# WX0_007_102DL.net
KiCad netlist of a schematic drawn in Altium Designer
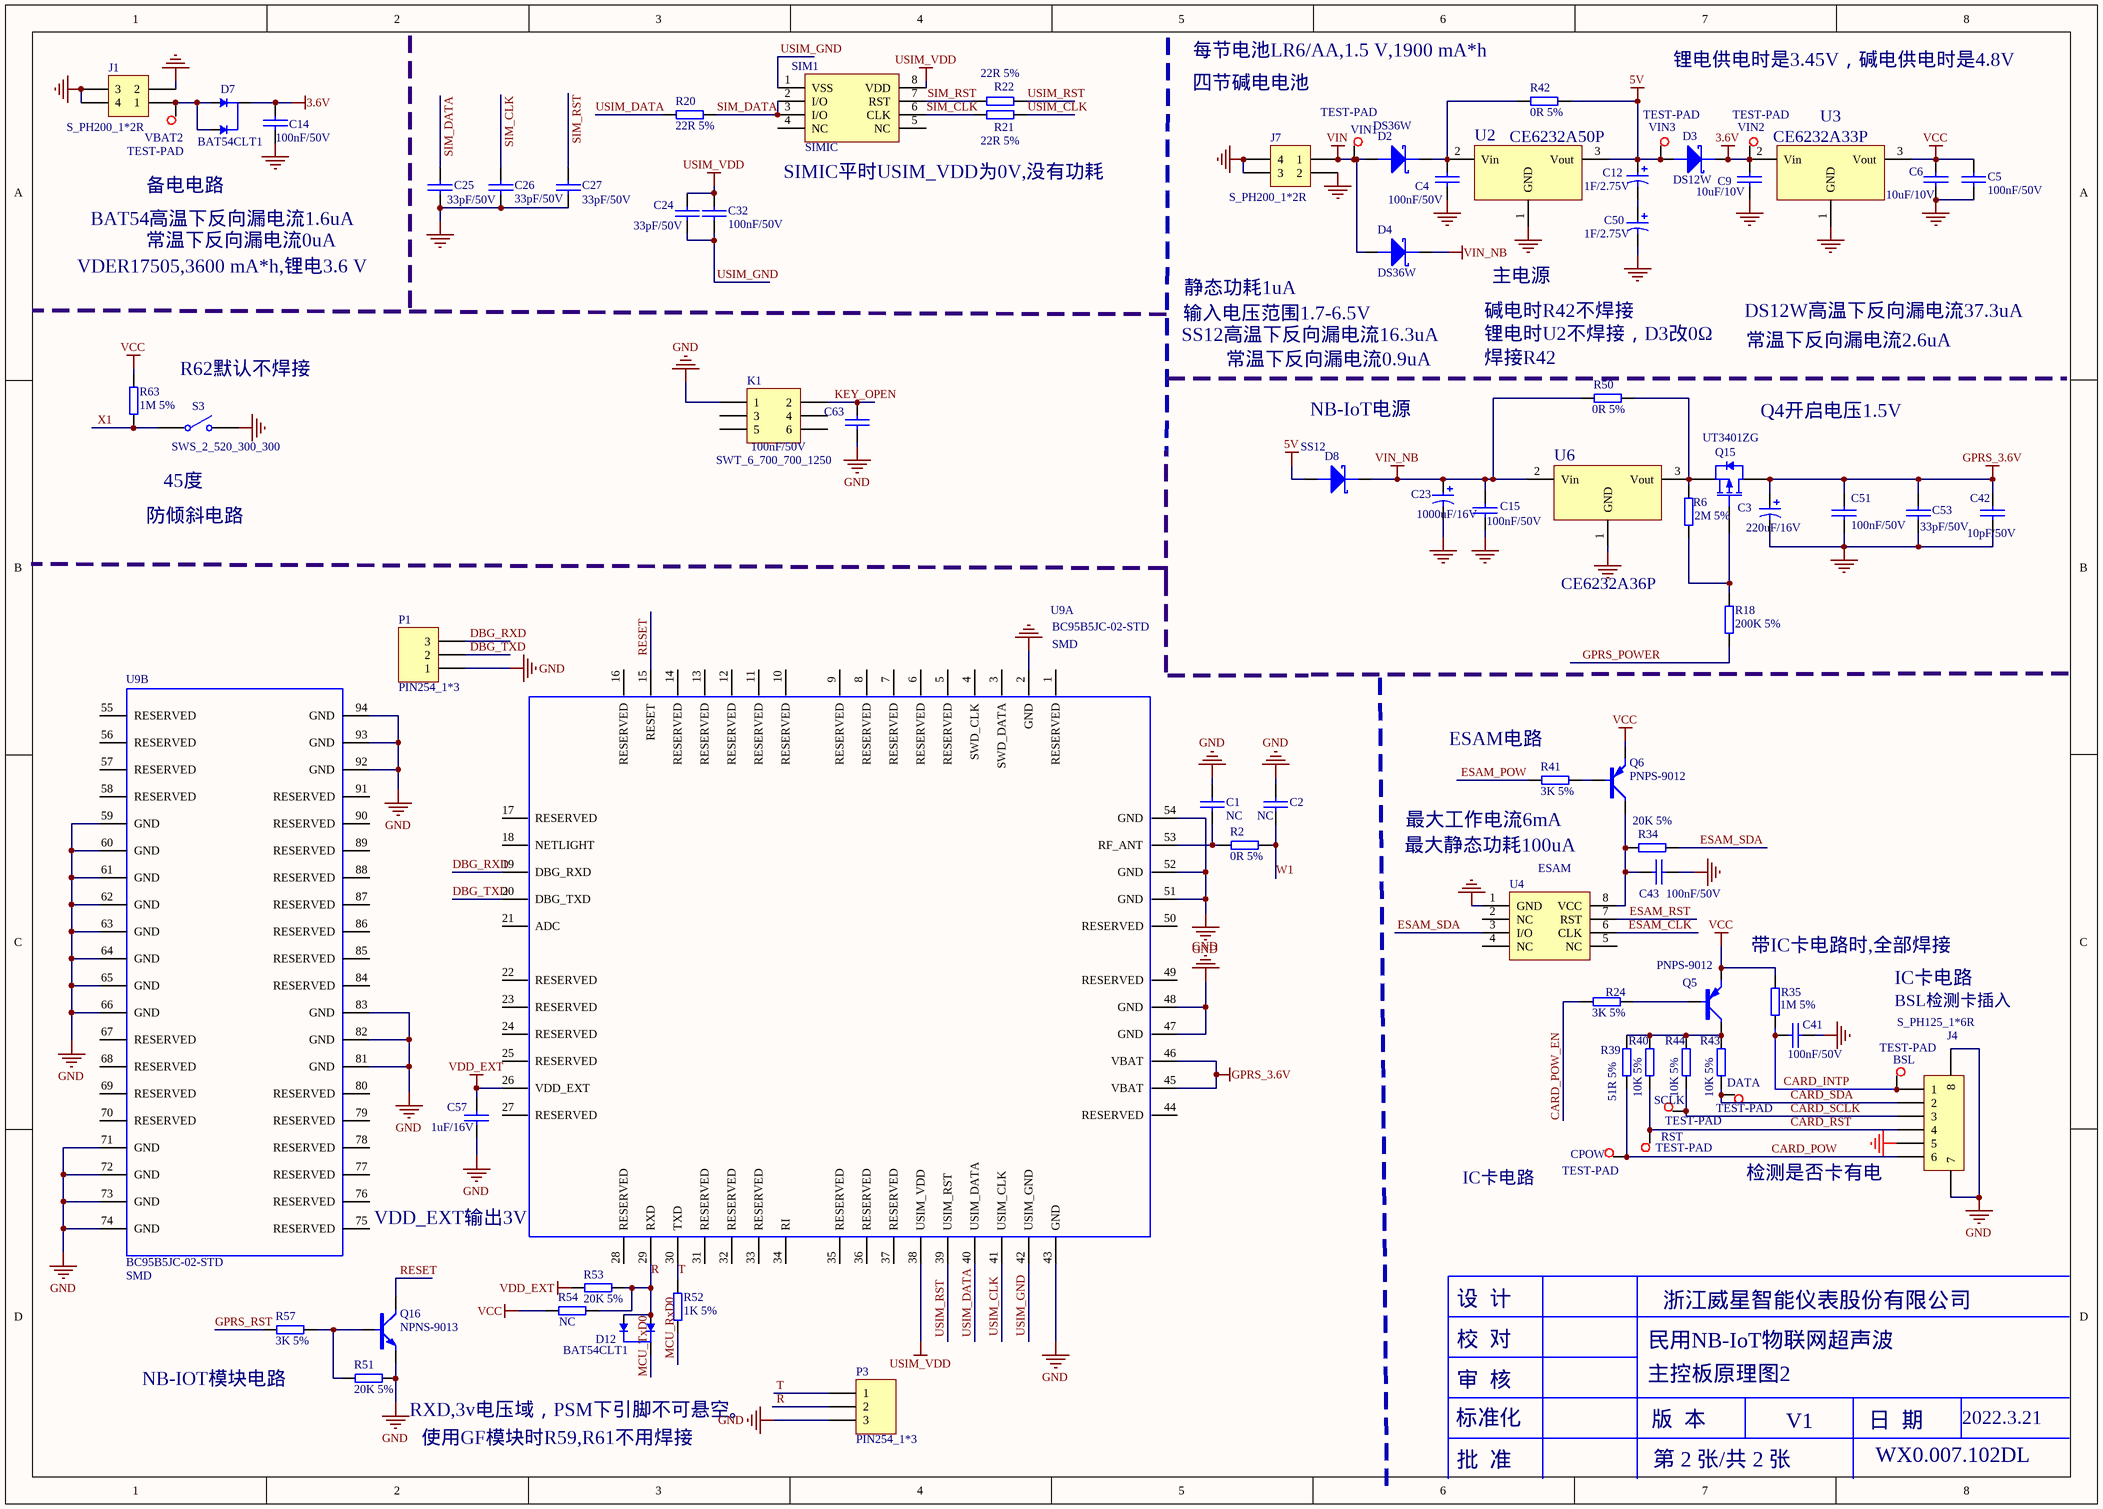
[diagram p0: WX0.007.102DL.SchDoc]

(export (version "E")
  (design (tool "Eeschema 10.0.6"))
  (components
    (comp (ref "BSL")
      (value "TEST-PAD")
      (footprint "TEST-PAD")
      (description "单面焊盘测试点")
      (fields (field (name "PART NUMBER") "AD_WXHJ_TEST-PAD_01"))
      (libsource (lib "Database_Libs2") (part "TEST-PAD"))
    )
    (comp (ref "C1")
      (value "NC")
      (footprint "CAP0603")
      (libsource (lib "Database_Libs2") (part "CC03JPO9_12P"))
    )
    (comp (ref "C2")
      (value "NC")
      (footprint "CAP0603")
      (libsource (lib "Database_Libs2") (part "CC03JPO9_12P"))
    )
    (comp (ref "C3")
      (value "220uF/16V")
      (footprint "220uf")
      (description "220UF")
      (fields (field (name "PART NUMBER") "1010203-0026"))
      (libsource (lib "Database_Libs2") (part "CAL7MRZLH_1000U_R"))
    )
    (comp (ref "C4")
      (value "100nF/50V")
      (footprint "CAP0603")
      (description "104pF,50 V,±10%,0603,国巨,CC0603KRX7R9BB104")
      (fields (field (name "PART NUMBER") "101020103-0021"))
      (libsource (lib "Database_Libs2") (part "CC03K7R9_100N"))
    )
    (comp (ref "C5")
      (value "100nF/50V")
      (footprint "CAP0603")
      (description "104pF,50 V,±10%,0603,国巨,CC0603KRX7R9BB104")
      (fields (field (name "PART NUMBER") "101020103-0021"))
      (libsource (lib "Database_Libs2") (part "CC03K7R9_100N"))
    )
    (comp (ref "C6")
      (value "10uF/10V")
      (footprint "CAP0603")
      (description "106pF,10 V,±10%,0603,村田,GRM188R61A106KE47D")
      (fields (field (name "PART NUMBER") "101020103-0026"))
      (libsource (lib "Database_Libs2") (part "CC03K5R6_10U"))
    )
    (comp (ref "C9")
      (value "10uF/10V")
      (footprint "CAP0603")
      (description "106pF,10 V,±10%,0603,村田,GRM188R61A106KE47D")
      (fields (field (name "PART NUMBER") "101020103-0026"))
      (libsource (lib "Database_Libs2") (part "CC03K5R6_10U"))
    )
    (comp (ref "C12")
      (value "1F/2.75V")
      (footprint "CE-8*11.5")
      (description "1F,2.75 V,-20%~+20%,8mm*16mm,红宝石,2.7 DMC 1 M MY4 8X16")
      (fields (field (name "PART NUMBER") "1010202-0015"))
      (libsource (lib "Database_Libs2") (part "CALM3MRDMC_1F"))
    )
    (comp (ref "C14")
      (value "100nF/50V")
      (footprint "CAP0603")
      (description "104pF,50 V,±10%,0603,国巨,CC0603KRX7R9BB104")
      (fields (field (name "PART NUMBER") "101020103-0021"))
      (libsource (lib "Database_Libs2") (part "CC03K7R9_100N"))
    )
    (comp (ref "C15")
      (value "100nF/50V")
      (footprint "CAP0603")
      (description "104pF,50 V,±10%,0603,国巨,CC0603KRX7R9BB104")
      (fields (field (name "PART NUMBER") "101020103-0021"))
      (libsource (lib "Database_Libs2") (part "CC03K7R9_100N"))
    )
    (comp (ref "C23")
      (value "1000uF/16V")
      (footprint "CAPSM_450_1000_1050")
      (description "1000UF,16V,±20%,贴片10*10.2MM,深圳市三炎科电子科技有限公司,16V1000UF")
      (fields (field (name "PART NUMBER") "1010203-0026"))
      (libsource (lib "Database_Libs2") (part "CAL7MRZLH_1000U_R"))
    )
    (comp (ref "C24")
      (value "33pF/50V")
      (footprint "CAP0603")
      (description "33pF,50 V,±10%,0603,国巨,CC0603KRNPO9BN33")
      (fields (field (name "PART NUMBER") "101020103-0027"))
      (libsource (lib "Database_Libs2") (part "CC03KPO9_33P"))
    )
    (comp (ref "C25")
      (value "33pF/50V")
      (footprint "CAP0603")
      (description "33pF,50 V,±10%,0603,国巨,CC0603KRNPO9BN33")
      (fields (field (name "PART NUMBER") "101020103-0027"))
      (libsource (lib "Database_Libs2") (part "CC03KPO9_33P"))
    )
    (comp (ref "C26")
      (value "33pF/50V")
      (footprint "CAP0603")
      (description "33pF,50 V,±10%,0603,国巨,CC0603KRNPO9BN33")
      (fields (field (name "PART NUMBER") "101020103-0027"))
      (libsource (lib "Database_Libs2") (part "CC03KPO9_33P"))
    )
    (comp (ref "C27")
      (value "33pF/50V")
      (footprint "CAP0603")
      (description "33pF,50 V,±10%,0603,国巨,CC0603KRNPO9BN33")
      (fields (field (name "PART NUMBER") "101020103-0027"))
      (libsource (lib "Database_Libs2") (part "CC03KPO9_33P"))
    )
    (comp (ref "C32")
      (value "100nF/50V")
      (footprint "CAP0603")
      (description "104pF,50 V,±10%,0603,国巨,CC0603KRX7R9BB104")
      (fields (field (name "PART NUMBER") "101020103-0021"))
      (libsource (lib "Database_Libs2") (part "CC03K7R9_100N"))
    )
    (comp (ref "C41")
      (value "100nF/50V")
      (footprint "CAP0603")
      (description "104pF,50 V,±10%,0603,国巨,CC0603KRX7R9BB104")
      (fields (field (name "PART NUMBER") "101020103-0021"))
      (libsource (lib "Database_Libs2") (part "CC03K7R9_100N"))
    )
    (comp (ref "C42")
      (value "10pF/50V")
      (footprint "CAP0603")
      (description "10pF,50 V,±5%,0603,X7R,国巨,CC0603JRNPO9BN100")
      (fields (field (name "PART NUMBER") "101020103-0014"))
      (libsource (lib "Database_Libs2") (part "CC03JPO9_10P"))
    )
    (comp (ref "C43")
      (value "100nF/50V")
      (footprint "CAP0603")
      (description "104pF,50 V,±10%,0603,国巨,CC0603KRX7R9BB104")
      (fields (field (name "PART NUMBER") "101020103-0021"))
      (libsource (lib "Database_Libs2") (part "CC03K7R9_100N"))
    )
    (comp (ref "C50")
      (value "1F/2.75V")
      (footprint "CE-8*11.5")
      (description "1F,2.75 V,-20%~+20%,8mm*16mm,红宝石,2.7 DMC 1 M MY4 8X16")
      (fields (field (name "PART NUMBER") "1010202-0015"))
      (libsource (lib "Database_Libs2") (part "CALM3MRDMC_1F"))
    )
    (comp (ref "C51")
      (value "100nF/50V")
      (footprint "CAP0603")
      (description "104pF,50 V,±10%,0603,国巨,CC0603KRX7R9BB104")
      (fields (field (name "PART NUMBER") "101020103-0021"))
      (libsource (lib "Database_Libs2") (part "CC03K7R9_100N"))
    )
    (comp (ref "C53")
      (value "33pF/50V")
      (footprint "CAP0603")
      (description "33pF,50 V,±10%,0603,国巨,CC0603KRNPO9BN33")
      (fields (field (name "PART NUMBER") "101020103-0027"))
      (libsource (lib "Database_Libs2") (part "CC03KPO9_33P"))
    )
    (comp (ref "C57")
      (value "1uF/16V")
      (footprint "CAP0603")
      (description "105pF,16 V,±10%,0603,国巨,CC0603KRX7R7BB105")
      (fields (field (name "PART NUMBER") "101020103-0003"))
      (libsource (lib "Database_Libs2") (part "CC03K7R7_1U"))
    )
    (comp (ref "C63")
      (value "100nF/50V")
      (footprint "CAP0603")
      (description "104pF,50 V,±10%,0603,国巨,CC0603KRX7R9BB104")
      (fields (field (name "PART NUMBER") "101020103-0021"))
      (libsource (lib "Database_Libs2") (part "CC03K7R9_100N"))
    )
    (comp (ref "CPOW")
      (value "TEST-PAD")
      (footprint "TEST-PAD")
      (description "单面焊盘测试点")
      (fields (field (name "PART NUMBER") "AD_WXHJ_TEST-PAD_01"))
      (libsource (lib "Database_Libs2") (part "TEST-PAD"))
    )
    (comp (ref "D2")
      (value "DS36W")
      (footprint "SOD-123FL")
      (description "DS36W,SOD123-FL,3 A,42 V,60 V,浙江领晨科技有限公司,DS36W")
      (fields (field (name "PART NUMBER") "101040101-0055"))
      (libsource (lib "Database_Libs2") (part "02_DS12W"))
    )
    (comp (ref "D3")
      (value "DS12W")
      (footprint "SOD-123FL")
      (description "DS12W,SOD-123FL,1 A,0.55 V,20 V,领晨科技,DS12W")
      (fields (field (name "PART NUMBER") "101040101-0048"))
      (libsource (lib "Database_Libs2") (part "02_DS12W"))
    )
    (comp (ref "D4")
      (value "DS36W")
      (footprint "SOD-123FL")
      (description "DS36W,SOD123-FL,3 A,42 V,60 V,浙江领晨科技有限公司,DS36W")
      (fields (field (name "PART NUMBER") "101040101-0055"))
      (libsource (lib "Database_Libs2") (part "02_DS36W"))
    )
    (comp (ref "D7")
      (value "BAT54CLT1")
      (footprint "SOT-23")
      (description "BAT54CLT1，SOT23-3,SOT23-3,0.2 A,0.8 V,30 V,安森美,BAT54CLT1")
      (fields (field (name "PART NUMBER") "101040101-0038"))
      (libsource (lib "Database_Libs2") (part "02_BAT54CLT1"))
    )
    (comp (ref "D8")
      (value "SS12")
      (footprint "DO-214AC")
      (description "SS12,DO-214AC,1 A,0.55 V,20 V,昶鑫,SS12")
      (fields (field (name "PART NUMBER") "101040101-0009"))
      (libsource (lib "Database_Libs2") (part "02_SS12"))
    )
    (comp (ref "D12")
      (value "BAT54CLT1")
      (footprint "SOT-23")
      (description "BAT54CLT1，SOT23-3,SOT23-3,0.2 A,0.8 V,30 V,安森美,BAT54CLT1")
      (fields (field (name "PART NUMBER") "101040101-0038"))
      (libsource (lib "Database_Libs2") (part "02_BAT54CLT1"))
    )
    (comp (ref "DATA")
      (value "TEST-PAD")
      (footprint "TEST-PAD")
      (description "单面焊盘测试点")
      (fields (field (name "PART NUMBER") "AD_WXHJ_TEST-PAD_01"))
      (libsource (lib "Database_Libs2") (part "TEST-PAD"))
    )
    (comp (ref "J1")
      (value "S_PH200_1*2R")
      (footprint "SMT2-2.0")
      (description "PH2.0_2AWR 卧,贴片卧式,母头,单排,2针2.0mm")
      (fields (field (name "PART NUMBER") "1010902-0125"))
      (libsource (lib "Database_Libs2") (part "S_PH200_1*2R"))
    )
    (comp (ref "J4")
      (value "S_PH125_1*6R")
      (footprint "SMT-1.25-6")
      (description "1.25-6AWR 卷,6针1.25mm,母头,单排,贴片卧式")
      (fields (field (name "PART NUMBER") "1010902-0121"))
      (libsource (lib "Database_Libs2") (part "S_PH125_1*6R"))
    )
    (comp (ref "J7")
      (value "S_PH200_1*2R")
      (footprint "SMT2-2.0")
      (description "PH2.0_2AWR 卧,贴片卧式,母头,单排,2针2.0mm")
      (fields (field (name "PART NUMBER") "1010902-0125"))
      (libsource (lib "") (part "S_PH200_1*2R_1"))
    )
    (comp (ref "K1")
      (value "SWT_6_700_700_1250")
      (footprint "KFT DIP-5.8X5.8")
      (description "7*7无锁按键,点触,7*7*12.5mm,7*7无锁按键,正立")
      (fields (field (name "PART NUMBER") "1011001-0037"))
      (libsource (lib "Database_Libs2") (part "07_SWT_6_700_700_1250"))
    )
    (comp (ref "P1")
      (value "PIN254_1*3")
      (footprint "PIN254_1*3*WXHJ")
      (libsource (lib "") (part "PIN254_1*3_1"))
    )
    (comp (ref "P3")
      (value "PIN254_1*3")
      (footprint "PIN254_1*3*WXHJ")
      (libsource (lib "Connect_WX") (part "PIN254_1*3"))
    )
    (comp (ref "Q5")
      (value "PNPS-9012")
      (footprint "SOT-23")
      (description "9012,PNP,SOT-23,JCET;长电,S9012")
      (fields (field (name "PART NUMBER") "101040201-0001"))
      (libsource (lib "Database_Libs2") (part "03_PNPS-9012"))
    )
    (comp (ref "Q6")
      (value "PNPS-9012")
      (footprint "SOT-23")
      (description "9012,PNP,SOT-23,JCET;长电,S9012")
      (fields (field (name "PART NUMBER") "101040201-0001"))
      (libsource (lib "Database_Libs2") (part "03_PNPS-9012"))
    )
    (comp (ref "Q15")
      (value "UT3401ZG")
      (footprint "SOT-23")
      (description "UT3401ZG,P-MOS,SOT-23,UTC,UT3401ZG")
      (fields (field (name "PART NUMBER") "101040201-0013"))
      (libsource (lib "Database_Libs2") (part "03_P-UT3401ZG"))
    )
    (comp (ref "Q16")
      (value "NPNS-9013")
      (footprint "SOT-23")
      (description "9013,NPN,SOT-23,长电,S9013")
      (fields (field (name "PART NUMBER") "101040201-0002"))
      (libsource (lib "Database_Libs2") (part "03_NPNS-9013"))
    )
    (comp (ref "R2")
      (value "0R 5%")
      (footprint "RES0603")
      (description "国巨,±5%,0603,,155 ℃,-55 ℃,RC0603J2-070RL,无铅,200 ppm/℃,1/10W,,0R")
      (fields (field (name "PART NUMBER") "101010103-0001"))
      (libsource (lib "Database_Libs2") (part "RC03J_0R"))
    )
    (comp (ref "R6")
      (value "2M 5%")
      (footprint "RES0603")
      (description "国巨,±5%,0603,,155 ℃,-55 ℃,RC0603JR-072ML,含铅,100 ppm/℃,1/10W,,2M")
      (fields (field (name "PART NUMBER") "101010103-0025"))
      (libsource (lib "Database_Libs2") (part "RC03J_2M"))
    )
    (comp (ref "R18")
      (value "200K 5%")
      (footprint "RES0603")
      (description "200K,±5%,1/10W,0603,国巨,RC0603JR-07200KL")
      (fields (field (name "PART NUMBER") "101010103-0034"))
      (libsource (lib "Database_Libs2") (part "RC03J_200K"))
    )
    (comp (ref "R20")
      (value "22R 5%")
      (footprint "RES0603")
      (description "国巨,±5%,0603,,155 ℃,-55 ℃,RC0603JR-0722RL,无铅,200 ppm/℃,1/10W,,22欧")
      (fields (field (name "PART NUMBER") "101010103-0009"))
      (libsource (lib "Database_Libs2") (part "RC03J_22R"))
    )
    (comp (ref "R21")
      (value "22R 5%")
      (footprint "RES0603")
      (description "国巨,±5%,0603,,155 ℃,-55 ℃,RC0603JR-0722RL,无铅,200 ppm/℃,1/10W,,22欧")
      (fields (field (name "PART NUMBER") "101010103-0009"))
      (libsource (lib "Database_Libs2") (part "RC03J_22R"))
    )
    (comp (ref "R22")
      (value "22R 5%")
      (footprint "RES0603")
      (description "国巨,±5%,0603,,155 ℃,-55 ℃,RC0603JR-0722RL,无铅,200 ppm/℃,1/10W,,22欧")
      (fields (field (name "PART NUMBER") "101010103-0009"))
      (libsource (lib "Database_Libs2") (part "RC03J_22R"))
    )
    (comp (ref "R24")
      (value "3K 5%")
      (footprint "RES0603")
      (description "国巨,±5%,0603,,155 ℃,-55 ℃,RC0603JR-073KL,无铅,100 ppm/℃,1/10W,,3K")
      (fields (field (name "PART NUMBER") "101010103-0006"))
      (libsource (lib "Database_Libs2") (part "RC03J_3K"))
    )
    (comp (ref "R34")
      (value "20K 5%")
      (footprint "RES0603")
      (description "国巨,±5%,0603,,155 ℃,-55 ℃,RC0603JR-0720KL,无铅,200 ppm/℃,1/10W,,20K")
      (fields (field (name "PART NUMBER") "101010103-0004"))
      (libsource (lib "Database_Libs2") (part "RC03J_20K"))
    )
    (comp (ref "R35")
      (value "1M 5%")
      (footprint "RES0603")
      (description "国巨,±5%,0603,,155 ℃,-55 ℃,RC0603JR-071ML,无铅,200 ppm/℃,1/10W,,1M")
      (fields (field (name "PART NUMBER") "101010103-0002"))
      (libsource (lib "Database_Libs2") (part "RC03J_1M"))
    )
    (comp (ref "R39")
      (value "51R 5%")
      (footprint "RES1206")
      (description "51Ω,±5%,1/4W,1206,国巨,RC1206JR-0751RL")
      (fields (field (name "PART NUMBER") "101010101-0029"))
      (libsource (lib "Database_Libs2") (part "RC06F_51R"))
    )
    (comp (ref "R40")
      (value "10K 5%")
      (footprint "RES0603")
      (description "国巨,±5%,0603,,155 ℃,-55 ℃,RC0603JR-0710KL,无铅,200 ppm/℃,1/10W,,10K")
      (fields (field (name "PART NUMBER") "101010103-0003"))
      (libsource (lib "Database_Libs2") (part "RC03J_10K"))
    )
    (comp (ref "R41")
      (value "3K 5%")
      (footprint "RES0603")
      (description "国巨,±5%,0603,,155 ℃,-55 ℃,RC0603JR-0710KL,无铅,200 ppm/℃,1/10W,,10K")
      (fields (field (name "PART NUMBER") "101010103-0003"))
      (libsource (lib "Database_Libs2") (part "RC03J_10K"))
    )
    (comp (ref "R42")
      (value "0R 5%")
      (footprint "RES1206")
      (description "0Ω,±5%,1/4W,1206,国巨,RC1206JR-070RL")
      (fields (field (name "PART NUMBER") "101010101-0013"))
      (libsource (lib "Database_Libs2") (part "RC06J_0R"))
    )
    (comp (ref "R43")
      (value "10K 5%")
      (footprint "RES0603")
      (description "国巨,±5%,0603,,155 ℃,-55 ℃,RC0603JR-0710KL,无铅,200 ppm/℃,1/10W,,10K")
      (fields (field (name "PART NUMBER") "101010103-0003"))
      (libsource (lib "Database_Libs2") (part "RC03J_10K"))
    )
    (comp (ref "R44")
      (value "10K 5%")
      (footprint "RES0603")
      (description "国巨,±5%,0603,,155 ℃,-55 ℃,RC0603JR-0710KL,无铅,200 ppm/℃,1/10W,,10K")
      (fields (field (name "PART NUMBER") "101010103-0003"))
      (libsource (lib "Database_Libs2") (part "RC03J_10K"))
    )
    (comp (ref "R50")
      (value "0R 5%")
      (footprint "RES1206")
      (description "0Ω,±5%,1/4W,1206,国巨,RC1206JR-070RL")
      (fields (field (name "PART NUMBER") "101010101-0013"))
      (libsource (lib "Database_Libs2") (part "RC06J_0R"))
    )
    (comp (ref "R51")
      (value "20K 5%")
      (footprint "RES0603")
      (description "国巨,±5%,0603,,155 ℃,-55 ℃,RC0603JR-0720KL,无铅,200 ppm/℃,1/10W,,20K")
      (fields (field (name "PART NUMBER") "101010103-0004"))
      (libsource (lib "Database_Libs2") (part "RC03J_20K"))
    )
    (comp (ref "R52")
      (value "1K 5%")
      (footprint "RES0603")
      (description "1K,±5%,1/10W,0603,国巨,RC0603JR-071KL")
      (fields (field (name "PART NUMBER") "101010103-0008"))
      (libsource (lib "Database_Libs2") (part "RC03J_1K"))
    )
    (comp (ref "R53")
      (value "20K 5%")
      (footprint "RES0603")
      (description "国巨,±5%,0603,,155 ℃,-55 ℃,RC0603JR-0720KL,无铅,200 ppm/℃,1/10W,,20K")
      (fields (field (name "PART NUMBER") "101010103-0004"))
      (libsource (lib "Database_Libs2") (part "RC03J_20K"))
    )
    (comp (ref "R54")
      (value "NC")
      (footprint "RES0603")
      (description "国巨,±5%,0603,,155 ℃,-55 ℃,RC0603JR-0720KL,无铅,200 ppm/℃,1/10W,,20K")
      (fields (field (name "PART NUMBER") "101010103-0004"))
      (libsource (lib "Database_Libs2") (part "RC03J_20K"))
    )
    (comp (ref "R57")
      (value "3K 5%")
      (footprint "RES0603")
      (description "国巨,±5%,0603,,155 ℃,-55 ℃,RC0603JR-073KL,无铅,100 ppm/℃,1/10W,,3K")
      (fields (field (name "PART NUMBER") "101010103-0006"))
      (libsource (lib "Database_Libs2") (part "RC03J_3K"))
    )
    (comp (ref "R63")
      (value "1M 5%")
      (footprint "RES0603")
      (description "国巨,±5%,0603,,155 ℃,-55 ℃,RC0603JR-071ML,无铅,200 ppm/℃,1/10W,,1M")
      (fields (field (name "PART NUMBER") "101010103-0002"))
      (libsource (lib "Database_Libs2") (part "RC03J_1M"))
    )
    (comp (ref "RST")
      (value "TEST-PAD")
      (footprint "TEST-PAD")
      (description "单面焊盘测试点")
      (fields (field (name "PART NUMBER") "AD_WXHJ_TEST-PAD_01"))
      (libsource (lib "Database_Libs2") (part "TEST-PAD"))
    )
    (comp (ref "S3")
      (value "SWS_2_520_300_300")
      (footprint "SWS_2_520_300")
      (description "CSX-SEN-645B,垂直45°开关转换,3*5.2mm,360°任意方位倾斜检测,深圳市成晟科技有限公司")
      (fields (field (name "PART NUMBER") "1011001-0051"))
      (libsource (lib "Database_Libs2") (part "07_SWS_2_520_300_300"))
    )
    (comp (ref "SCLK")
      (value "TEST-PAD")
      (footprint "TEST-PAD")
      (description "单面焊盘测试点")
      (fields (field (name "PART NUMBER") "AD_WXHJ_TEST-PAD_01"))
      (libsource (lib "Database_Libs2") (part "TEST-PAD"))
    )
    (comp (ref "SIM1")
      (value "SIMIC")
      (footprint "SIMIC")
      (description "SIMIC虚拟器件")
      (fields (field (name "PART NUMBER") "AD_XN_SIMIC_01"))
      (libsource (lib "Database_Libs2") (part "05_SIMIC"))
    )
    (comp (ref "U2")
      (value "CE6232A50P")
      (footprint "SOT-89")
      (fields (field (name "PART NUMBER") "1010503-0013"))
      (libsource (lib "Database_Libs2") (part "02_S-1206B50-U3"))
    )
    (comp (ref "U3")
      (value "CE6232A33P")
      (footprint "SOT-89")
      (fields (field (name "PART NUMBER") "1010503-0002"))
      (libsource (lib "Database_Libs2") (part "02_S-1206B33-U3T1G"))
    )
    (comp (ref "U4")
      (value "ESAM")
      (footprint "SOP-8")
      (description "ESAM虚拟器件")
      (fields (field (name "PART NUMBER") "AD_XN_ESAM_01"))
      (libsource (lib "Database_Libs2") (part "04_ESAM"))
    )
    (comp (ref "U6")
      (value "CE6232A36P")
      (footprint "SOT-89")
      (description "CE6232A36P,CE6232A36P,SOT89-3,8 V,1.8 V,0.11 V,3.6 V,600mA,0.8 uA,南京芯力微电子有限公司")
      (fields (field (name "PART NUMBER") "1010503-0031"))
      (libsource (lib "Database_Libs2") (part "02_CE6232A36P"))
    )
    (comp (ref "U9")
      (value "BC95B5JC-02-STD")
      (footprint "BC95B5JC-02-STD")
      (description "BC95-B5,23.6mm*19.9mm*2.2mm,BC95B5JC-02-STD,LCC贴片封装,上海移远通信技术股份")
      (fields (field (name "PART NUMBER") "1011402-0141") (field (name "SMD/DIP") "SMD"))
      (libsource (lib "Database_Libs2") (part "01_BC95B5JC-02-STD"))
    )
    (comp (ref "VBAT2")
      (value "TEST-PAD")
      (footprint "TEST-PAD")
      (description "单面焊盘测试点")
      (fields (field (name "PART NUMBER") "AD_WXHJ_TEST-PAD_01"))
      (libsource (lib "Database_Libs2") (part "TEST-PAD"))
    )
    (comp (ref "VIN1")
      (value "TEST-PAD")
      (footprint "TEST-PAD")
      (description "单面焊盘测试点")
      (fields (field (name "PART NUMBER") "AD_WXHJ_TEST-PAD_01"))
      (libsource (lib "Database_Libs2") (part "TEST-PAD"))
    )
    (comp (ref "VIN2")
      (value "TEST-PAD")
      (footprint "TEST-PAD")
      (description "单面焊盘测试点")
      (fields (field (name "PART NUMBER") "AD_WXHJ_TEST-PAD_01"))
      (libsource (lib "Database_Libs2") (part "TEST-PAD"))
    )
    (comp (ref "VIN3")
      (value "TEST-PAD")
      (footprint "TEST-PAD")
      (description "单面焊盘测试点")
      (fields (field (name "PART NUMBER") "AD_WXHJ_TEST-PAD_01"))
      (libsource (lib "Database_Libs2") (part "TEST-PAD"))
    )
  )
  (nets
    (net (code "1") (name "/CARD_INTP") (class "Default")
      (node (ref "BSL") (pin "1") (pinfunction "1_1") (pintype "passive"))
      (node (ref "C41") (pin "1") (pinfunction "1_1") (pintype "passive"))
      (node (ref "J4") (pin "1") (pinfunction "1_1") (pintype "passive"))
      (node (ref "R35") (pin "1") (pinfunction "1_1") (pintype "passive"))
    )
    (net (code "2") (name "/CARD_POW") (class "Default")
      (node (ref "CPOW") (pin "1") (pinfunction "1_1") (pintype "passive"))
      (node (ref "J4") (pin "6") (pinfunction "6_6") (pintype "passive"))
      (node (ref "R39") (pin "1") (pinfunction "1_1") (pintype "passive"))
    )
    (net (code "3") (name "/CARD_POW_EN") (class "Default")
      (node (ref "R24") (pin "1") (pinfunction "1_1") (pintype "passive"))
    )
    (net (code "4") (name "/CARD_RST") (class "Default")
      (node (ref "J4") (pin "4") (pinfunction "4_4") (pintype "passive"))
      (node (ref "R40") (pin "1") (pinfunction "1_1") (pintype "passive"))
      (node (ref "RST") (pin "1") (pinfunction "1_1") (pintype "passive"))
    )
    (net (code "5") (name "/CARD_SCLK") (class "Default")
      (node (ref "J4") (pin "3") (pinfunction "3_3") (pintype "passive"))
      (node (ref "R44") (pin "1") (pinfunction "1_1") (pintype "passive"))
      (node (ref "SCLK") (pin "1") (pinfunction "1_1") (pintype "passive"))
    )
    (net (code "6") (name "/CARD_SDA") (class "Default")
      (node (ref "DATA") (pin "1") (pinfunction "1_1") (pintype "passive"))
      (node (ref "J4") (pin "2") (pinfunction "2_2") (pintype "passive"))
      (node (ref "R43") (pin "1") (pinfunction "1_1") (pintype "passive"))
    )
    (net (code "7") (name "/DBG_RXD") (class "Default")
      (node (ref "P1") (pin "3") (pinfunction "3_3") (pintype "passive"))
      (node (ref "U9") (pin "19") (pinfunction "DBG_RXD_19") (pintype "passive"))
    )
    (net (code "8") (name "/DBG_TXD") (class "Default")
      (node (ref "P1") (pin "2") (pinfunction "2_2") (pintype "passive"))
      (node (ref "U9") (pin "20") (pinfunction "DBG_TXD_20") (pintype "passive"))
    )
    (net (code "9") (name "/ESAM_CLK") (class "Default")
      (node (ref "U4") (pin "6") (pinfunction "CLK_6") (pintype "passive"))
    )
    (net (code "10") (name "/ESAM_POW") (class "Default")
      (node (ref "R41") (pin "1") (pinfunction "1_1") (pintype "passive"))
    )
    (net (code "11") (name "/ESAM_RST") (class "Default")
      (node (ref "U4") (pin "7") (pinfunction "RST_7") (pintype "passive"))
    )
    (net (code "12") (name "/ESAM_SDA") (class "Default")
      (node (ref "R34") (pin "2") (pinfunction "2_2") (pintype "passive"))
      (node (ref "U4") (pin "3") (pinfunction "I/O_3") (pintype "passive"))
    )
    (net (code "13") (name "/GPRS_POWER") (class "Default")
      (node (ref "R18") (pin "1") (pinfunction "1_1") (pintype "passive"))
    )
    (net (code "14") (name "/GPRS_RST") (class "Default")
      (node (ref "R57") (pin "1") (pinfunction "1_1") (pintype "passive"))
    )
    (net (code "15") (name "/KEY_OPEN") (class "Default")
      (node (ref "C63") (pin "2") (pinfunction "2_2") (pintype "passive"))
      (node (ref "K1") (pin "2") (pinfunction "2_2") (pintype "passive"))
    )
    (net (code "16") (name "/MCU_RxD0") (class "Default")
      (node (ref "R52") (pin "1") (pinfunction "1_1") (pintype "passive"))
    )
    (net (code "17") (name "/MCU_TxD0") (class "Default")
      (node (ref "D12") (pin "3") (pinfunction "C_3") (pintype "passive"))
    )
    (net (code "18") (name "/R") (class "Default")
      (node (ref "D12") (pin "1") (pinfunction "A_1") (pintype "passive"))
      (node (ref "D12") (pin "2") (pinfunction "A_2") (pintype "passive"))
      (node (ref "P3") (pin "2") (pinfunction "2_2") (pintype "passive"))
      (node (ref "R53") (pin "2") (pinfunction "2_2") (pintype "passive"))
      (node (ref "R54") (pin "2") (pinfunction "2_2") (pintype "passive"))
      (node (ref "U9") (pin "29") (pinfunction "RXD_29") (pintype "passive"))
    )
    (net (code "19") (name "/RESET") (class "Default")
      (node (ref "Q16") (pin "3") (pinfunction "C_3") (pintype "passive"))
      (node (ref "U9") (pin "15") (pinfunction "RESET_15") (pintype "passive"))
    )
    (net (code "20") (name "/SIM_CLK") (class "Default")
      (node (ref "C26") (pin "1") (pinfunction "1_1") (pintype "passive"))
      (node (ref "R21") (pin "1") (pinfunction "1_1") (pintype "passive"))
      (node (ref "SIM1") (pin "6") (pinfunction "CLK_6") (pintype "passive"))
    )
    (net (code "21") (name "/SIM_DATA") (class "Default")
      (node (ref "C25") (pin "1") (pinfunction "1_1") (pintype "passive"))
      (node (ref "R20") (pin "2") (pinfunction "2_2") (pintype "passive"))
      (node (ref "SIM1") (pin "2") (pinfunction "I/O_2") (pintype "passive"))
      (node (ref "SIM1") (pin "3") (pinfunction "I/O_3") (pintype "passive"))
    )
    (net (code "22") (name "/SIM_RST") (class "Default")
      (node (ref "C27") (pin "1") (pinfunction "1_1") (pintype "passive"))
      (node (ref "R22") (pin "1") (pinfunction "1_1") (pintype "passive"))
      (node (ref "SIM1") (pin "7") (pinfunction "RST_7") (pintype "passive"))
    )
    (net (code "23") (name "/T") (class "Default")
      (node (ref "P3") (pin "1") (pinfunction "1_1") (pintype "passive"))
      (node (ref "R52") (pin "2") (pinfunction "2_2") (pintype "passive"))
      (node (ref "U9") (pin "30") (pinfunction "TXD_30") (pintype "passive"))
    )
    (net (code "24") (name "/USIM_CLK") (class "Default")
      (node (ref "R21") (pin "2") (pinfunction "2_2") (pintype "passive"))
      (node (ref "U9") (pin "41") (pinfunction "USIM_CLK_41") (pintype "passive"))
    )
    (net (code "25") (name "/USIM_DATA") (class "Default")
      (node (ref "R20") (pin "1") (pinfunction "1_1") (pintype "passive"))
      (node (ref "U9") (pin "40") (pinfunction "USIM_DATA_40") (pintype "passive"))
    )
    (net (code "26") (name "/USIM_GND") (class "Default")
      (node (ref "C24") (pin "2") (pinfunction "2_2") (pintype "passive"))
      (node (ref "C32") (pin "2") (pinfunction "2_2") (pintype "passive"))
      (node (ref "SIM1") (pin "1") (pinfunction "VSS_1") (pintype "passive"))
      (node (ref "U9") (pin "42") (pinfunction "USIM_GND_42") (pintype "passive"))
    )
    (net (code "27") (name "/USIM_RST") (class "Default")
      (node (ref "R22") (pin "2") (pinfunction "2_2") (pintype "passive"))
      (node (ref "U9") (pin "39") (pinfunction "USIM_RST_39") (pintype "passive"))
    )
    (net (code "28") (name "/W1") (class "Default")
      (node (ref "C2") (pin "1") (pinfunction "1_1") (pintype "passive"))
      (node (ref "R2") (pin "1") (pinfunction "1_1") (pintype "passive"))
    )
    (net (code "29") (name "/X1") (class "Default")
      (node (ref "R63") (pin "1") (pinfunction "1_1") (pintype "passive"))
      (node (ref "S3") (pin "1") (pintype "passive"))
    )
    (net (code "30") (name "3.6V") (class "Default")
      (node (ref "C14") (pin "1") (pinfunction "1_1") (pintype "passive"))
      (node (ref "C9") (pin "1") (pinfunction "1_1") (pintype "passive"))
      (node (ref "D3") (pin "2") (pinfunction "2_2") (pintype "passive"))
      (node (ref "D7") (pin "3") (pinfunction "C_3") (pintype "passive"))
      (node (ref "U3") (pin "2") (pinfunction "Vin_2") (pintype "passive"))
      (node (ref "VIN2") (pin "1") (pinfunction "1_1") (pintype "passive"))
    )
    (net (code "31") (name "5V") (class "Default")
      (node (ref "C12") (pin "1") (pinfunction "1_1") (pintype "passive"))
      (node (ref "D3") (pin "1") (pinfunction "1_1") (pintype "passive"))
      (node (ref "D8") (pin "1") (pinfunction "1_1") (pintype "passive"))
      (node (ref "R42") (pin "2") (pinfunction "2_2") (pintype "passive"))
      (node (ref "U2") (pin "3") (pinfunction "Vout_3") (pintype "passive"))
      (node (ref "VIN3") (pin "1") (pinfunction "1_1") (pintype "passive"))
    )
    (net (code "32") (name "GND") (class "Default")
      (node (ref "C1") (pin "2") (pinfunction "2_2") (pintype "passive"))
      (node (ref "C14") (pin "2") (pinfunction "2_2") (pintype "passive"))
      (node (ref "C15") (pin "2") (pinfunction "2_2") (pintype "passive"))
      (node (ref "C2") (pin "2") (pinfunction "2_2") (pintype "passive"))
      (node (ref "C23") (pin "2") (pinfunction "2_2") (pintype "passive"))
      (node (ref "C25") (pin "2") (pinfunction "2_2") (pintype "passive"))
      (node (ref "C26") (pin "2") (pinfunction "2_2") (pintype "passive"))
      (node (ref "C27") (pin "2") (pinfunction "2_2") (pintype "passive"))
      (node (ref "C3") (pin "2") (pinfunction "2_2") (pintype "passive"))
      (node (ref "C4") (pin "2") (pinfunction "2_2") (pintype "passive"))
      (node (ref "C41") (pin "2") (pinfunction "2_2") (pintype "passive"))
      (node (ref "C42") (pin "2") (pinfunction "2_2") (pintype "passive"))
      (node (ref "C43") (pin "2") (pinfunction "2_2") (pintype "passive"))
      (node (ref "C5") (pin "2") (pinfunction "2_2") (pintype "passive"))
      (node (ref "C50") (pin "2") (pinfunction "2_2") (pintype "passive"))
      (node (ref "C51") (pin "2") (pinfunction "2_2") (pintype "passive"))
      (node (ref "C53") (pin "2") (pinfunction "2_2") (pintype "passive"))
      (node (ref "C57") (pin "2") (pinfunction "2_2") (pintype "passive"))
      (node (ref "C6") (pin "2") (pinfunction "2_2") (pintype "passive"))
      (node (ref "C63") (pin "1") (pinfunction "1_1") (pintype "passive"))
      (node (ref "C9") (pin "2") (pinfunction "2_2") (pintype "passive"))
      (node (ref "J1") (pin "2") (pinfunction "2_2") (pintype "passive"))
      (node (ref "J1") (pin "3") (pinfunction "3_3") (pintype "passive"))
      (node (ref "J1") (pin "4") (pinfunction "4_4") (pintype "passive"))
      (node (ref "J4") (pin "5") (pinfunction "5_5") (pintype "passive"))
      (node (ref "J4") (pin "7") (pinfunction "7_7") (pintype "passive"))
      (node (ref "J4") (pin "8") (pinfunction "8_8") (pintype "passive"))
      (node (ref "J7") (pin "2") (pinfunction "2_2") (pintype "passive"))
      (node (ref "J7") (pin "3") (pinfunction "3_3") (pintype "passive"))
      (node (ref "J7") (pin "4") (pinfunction "4_4") (pintype "passive"))
      (node (ref "K1") (pin "1") (pinfunction "1_1") (pintype "passive"))
      (node (ref "P1") (pin "1") (pinfunction "1_1") (pintype "passive"))
      (node (ref "P3") (pin "3") (pinfunction "3_3") (pintype "passive"))
      (node (ref "Q16") (pin "2") (pinfunction "E_2") (pintype "passive"))
      (node (ref "R51") (pin "2") (pinfunction "2_2") (pintype "passive"))
      (node (ref "S3") (pin "2") (pintype "passive"))
      (node (ref "U2") (pin "1") (pinfunction "GND_1") (pintype "passive"))
      (node (ref "U3") (pin "1") (pinfunction "GND_1") (pintype "passive"))
      (node (ref "U4") (pin "1") (pinfunction "GND_1") (pintype "passive"))
      (node (ref "U6") (pin "1") (pinfunction "GND_1") (pintype "passive"))
      (node (ref "U9") (pin "2") (pinfunction "GND_2") (pintype "passive"))
      (node (ref "U9") (pin "43") (pinfunction "GND_43") (pintype "passive"))
      (node (ref "U9") (pin "47") (pinfunction "GND_47") (pintype "passive"))
      (node (ref "U9") (pin "48") (pinfunction "GND_48") (pintype "passive"))
      (node (ref "U9") (pin "51") (pinfunction "GND_51") (pintype "passive"))
      (node (ref "U9") (pin "52") (pinfunction "GND_52") (pintype "passive"))
      (node (ref "U9") (pin "54") (pinfunction "GND_54") (pintype "passive"))
      (node (ref "U9") (pin "59") (pinfunction "GND_59") (pintype "passive"))
      (node (ref "U9") (pin "60") (pinfunction "GND_60") (pintype "passive"))
      (node (ref "U9") (pin "61") (pinfunction "GND_61") (pintype "passive"))
      (node (ref "U9") (pin "62") (pinfunction "GND_62") (pintype "passive"))
      (node (ref "U9") (pin "63") (pinfunction "GND_63") (pintype "passive"))
      (node (ref "U9") (pin "64") (pinfunction "GND_64") (pintype "passive"))
      (node (ref "U9") (pin "65") (pinfunction "GND_65") (pintype "passive"))
      (node (ref "U9") (pin "66") (pinfunction "GND_66") (pintype "passive"))
      (node (ref "U9") (pin "71") (pinfunction "GND_71") (pintype "passive"))
      (node (ref "U9") (pin "72") (pinfunction "GND_72") (pintype "passive"))
      (node (ref "U9") (pin "73") (pinfunction "GND_73") (pintype "passive"))
      (node (ref "U9") (pin "74") (pinfunction "GND_74") (pintype "passive"))
      (node (ref "U9") (pin "81") (pinfunction "GND_81") (pintype "passive"))
      (node (ref "U9") (pin "82") (pinfunction "GND_82") (pintype "passive"))
      (node (ref "U9") (pin "83") (pinfunction "GND_83") (pintype "passive"))
      (node (ref "U9") (pin "92") (pinfunction "GND_92") (pintype "passive"))
      (node (ref "U9") (pin "93") (pinfunction "GND_93") (pintype "passive"))
      (node (ref "U9") (pin "94") (pinfunction "GND_94") (pintype "passive"))
    )
    (net (code "33") (name "GPRS_3.6V") (class "Default")
      (node (ref "C3") (pin "1") (pinfunction "1_1") (pintype "passive"))
      (node (ref "C42") (pin "1") (pinfunction "1_1") (pintype "passive"))
      (node (ref "C51") (pin "1") (pinfunction "1_1") (pintype "passive"))
      (node (ref "C53") (pin "1") (pinfunction "1_1") (pintype "passive"))
      (node (ref "Q15") (pin "3") (pinfunction "D_3") (pintype "passive"))
      (node (ref "U9") (pin "45") (pinfunction "VBAT_45") (pintype "passive"))
      (node (ref "U9") (pin "46") (pinfunction "VBAT_46") (pintype "passive"))
    )
    (net (code "34") (name "Net-(C12-Pad2)") (class "Default")
      (node (ref "C12") (pin "2") (pinfunction "2_2") (pintype "passive"))
      (node (ref "C50") (pin "1") (pinfunction "1_1") (pintype "passive"))
    )
    (net (code "35") (name "Net-(D7-A-Pad1)") (class "Default")
      (node (ref "D7") (pin "1") (pinfunction "A_1") (pintype "passive"))
      (node (ref "D7") (pin "2") (pinfunction "A_2") (pintype "passive"))
      (node (ref "J1") (pin "1") (pinfunction "1_1") (pintype "passive"))
      (node (ref "VBAT2") (pin "1") (pinfunction "1_1") (pintype "passive"))
    )
    (net (code "36") (name "Net-(Q5-B)") (class "Default")
      (node (ref "Q5") (pin "1") (pinfunction "B_1") (pintype "passive"))
      (node (ref "R24") (pin "2") (pinfunction "2_2") (pintype "passive"))
    )
    (net (code "37") (name "Net-(Q5-C)") (class "Default")
      (node (ref "Q5") (pin "3") (pinfunction "C_3") (pintype "passive"))
      (node (ref "R39") (pin "2") (pinfunction "2_2") (pintype "passive"))
      (node (ref "R40") (pin "2") (pinfunction "2_2") (pintype "passive"))
      (node (ref "R43") (pin "2") (pinfunction "2_2") (pintype "passive"))
      (node (ref "R44") (pin "2") (pinfunction "2_2") (pintype "passive"))
    )
    (net (code "38") (name "Net-(Q6-B)") (class "Default")
      (node (ref "Q6") (pin "1") (pinfunction "B_1") (pintype "passive"))
      (node (ref "R41") (pin "2") (pinfunction "2_2") (pintype "passive"))
    )
    (net (code "39") (name "Net-(Q6-C)") (class "Default")
      (node (ref "C43") (pin "1") (pinfunction "1_1") (pintype "passive"))
      (node (ref "Q6") (pin "3") (pinfunction "C_3") (pintype "passive"))
      (node (ref "R34") (pin "1") (pinfunction "1_1") (pintype "passive"))
      (node (ref "U4") (pin "8") (pinfunction "VCC_8") (pintype "passive"))
    )
    (net (code "40") (name "Net-(Q15-G)") (class "Default")
      (node (ref "Q15") (pin "1") (pinfunction "G_1") (pintype "passive"))
      (node (ref "R18") (pin "2") (pinfunction "2_2") (pintype "passive"))
      (node (ref "R6") (pin "1") (pinfunction "1_1") (pintype "passive"))
    )
    (net (code "41") (name "Net-(Q15-S)") (class "Default")
      (node (ref "Q15") (pin "2") (pinfunction "S_2") (pintype "passive"))
      (node (ref "R50") (pin "2") (pinfunction "2_2") (pintype "passive"))
      (node (ref "R6") (pin "2") (pinfunction "2_2") (pintype "passive"))
      (node (ref "U6") (pin "3") (pinfunction "Vout_3") (pintype "passive"))
    )
    (net (code "42") (name "Net-(Q16-B)") (class "Default")
      (node (ref "Q16") (pin "1") (pinfunction "B_1") (pintype "passive"))
      (node (ref "R51") (pin "1") (pinfunction "1_1") (pintype "passive"))
      (node (ref "R57") (pin "2") (pinfunction "2_2") (pintype "passive"))
    )
    (net (code "43") (name "Net-(U2-Vin)") (class "Default")
      (node (ref "C4") (pin "1") (pinfunction "1_1") (pintype "passive"))
      (node (ref "D2") (pin "2") (pinfunction "2_2") (pintype "passive"))
      (node (ref "R42") (pin "1") (pinfunction "1_1") (pintype "passive"))
      (node (ref "U2") (pin "2") (pinfunction "Vin_2") (pintype "passive"))
    )
    (net (code "44") (name "Net-(U9A-RF_ANT)") (class "Default")
      (node (ref "C1") (pin "1") (pinfunction "1_1") (pintype "passive"))
      (node (ref "R2") (pin "2") (pinfunction "2_2") (pintype "passive"))
      (node (ref "U9") (pin "53") (pinfunction "RF_ANT_53") (pintype "passive"))
    )
    (net (code "45") (name "USIM_VDD") (class "Default")
      (node (ref "C24") (pin "1") (pinfunction "1_1") (pintype "passive"))
      (node (ref "C32") (pin "1") (pinfunction "1_1") (pintype "passive"))
      (node (ref "SIM1") (pin "8") (pinfunction "VDD_8") (pintype "passive"))
      (node (ref "U9") (pin "38") (pinfunction "USIM_VDD_38") (pintype "passive"))
    )
    (net (code "46") (name "VCC") (class "Default")
      (node (ref "C5") (pin "1") (pinfunction "1_1") (pintype "passive"))
      (node (ref "C6") (pin "1") (pinfunction "1_1") (pintype "passive"))
      (node (ref "Q5") (pin "2") (pinfunction "E_2") (pintype "passive"))
      (node (ref "Q6") (pin "2") (pinfunction "E_2") (pintype "passive"))
      (node (ref "R35") (pin "2") (pinfunction "2_2") (pintype "passive"))
      (node (ref "R54") (pin "1") (pinfunction "1_1") (pintype "passive"))
      (node (ref "R63") (pin "2") (pinfunction "2_2") (pintype "passive"))
      (node (ref "U3") (pin "3") (pinfunction "Vout_3") (pintype "passive"))
    )
    (net (code "47") (name "VDD_EXT") (class "Default")
      (node (ref "C57") (pin "1") (pinfunction "1_1") (pintype "passive"))
      (node (ref "R53") (pin "1") (pinfunction "1_1") (pintype "passive"))
      (node (ref "U9") (pin "26") (pinfunction "VDD_EXT_26") (pintype "passive"))
    )
    (net (code "48") (name "VIN") (class "Default")
      (node (ref "D2") (pin "1") (pinfunction "1_1") (pintype "passive"))
      (node (ref "D4") (pin "1") (pinfunction "1_1") (pintype "passive"))
      (node (ref "J7") (pin "1") (pinfunction "1_1") (pintype "passive"))
      (node (ref "VIN1") (pin "1") (pinfunction "1_1") (pintype "passive"))
    )
    (net (code "49") (name "VIN_NB") (class "Default")
      (node (ref "C15") (pin "1") (pinfunction "1_1") (pintype "passive"))
      (node (ref "C23") (pin "1") (pinfunction "1_1") (pintype "passive"))
      (node (ref "D4") (pin "2") (pinfunction "2_2") (pintype "passive"))
      (node (ref "D8") (pin "2") (pinfunction "2_2") (pintype "passive"))
      (node (ref "R50") (pin "1") (pinfunction "1_1") (pintype "passive"))
      (node (ref "U6") (pin "2") (pinfunction "Vin_2") (pintype "passive"))
    )
    (net (code "50") (name "unconnected-(K1-Pad3)") (class "Default")
      (node (ref "K1") (pin "3") (pinfunction "3_3") (pintype "passive"))
    )
    (net (code "51") (name "unconnected-(K1-Pad4)") (class "Default")
      (node (ref "K1") (pin "4") (pinfunction "4_4") (pintype "passive"))
    )
    (net (code "52") (name "unconnected-(K1-Pad5)") (class "Default")
      (node (ref "K1") (pin "5") (pinfunction "5_5") (pintype "passive"))
    )
    (net (code "53") (name "unconnected-(K1-Pad6)") (class "Default")
      (node (ref "K1") (pin "6") (pinfunction "6_6") (pintype "passive"))
    )
    (net (code "54") (name "unconnected-(SIM1-NC-Pad4)") (class "Default")
      (node (ref "SIM1") (pin "4") (pinfunction "NC_4") (pintype "passive"))
    )
    (net (code "55") (name "unconnected-(SIM1-NC-Pad5)") (class "Default")
      (node (ref "SIM1") (pin "5") (pinfunction "NC_5") (pintype "passive"))
    )
    (net (code "56") (name "unconnected-(U4-NC-Pad2)") (class "Default")
      (node (ref "U4") (pin "2") (pinfunction "NC_2") (pintype "passive"))
    )
    (net (code "57") (name "unconnected-(U4-NC-Pad4)") (class "Default")
      (node (ref "U4") (pin "4") (pinfunction "NC_4") (pintype "passive"))
    )
    (net (code "58") (name "unconnected-(U4-NC-Pad5)") (class "Default")
      (node (ref "U4") (pin "5") (pinfunction "NC_5") (pintype "passive"))
    )
    (net (code "59") (name "unconnected-(U9A-ADC-Pad21)") (class "Default")
      (node (ref "U9") (pin "21") (pinfunction "ADC_21") (pintype "passive"))
    )
    (net (code "60") (name "unconnected-(U9A-NETLIGHT-Pad18)") (class "Default")
      (node (ref "U9") (pin "18") (pinfunction "NETLIGHT_18") (pintype "passive"))
    )
    (net (code "61") (name "unconnected-(U9A-RESERVED-Pad1)") (class "Default")
      (node (ref "U9") (pin "1") (pinfunction "RESERVED_1") (pintype "passive"))
    )
    (net (code "62") (name "unconnected-(U9A-RESERVED-Pad5)") (class "Default")
      (node (ref "U9") (pin "5") (pinfunction "RESERVED_5") (pintype "passive"))
    )
    (net (code "63") (name "unconnected-(U9A-RESERVED-Pad6)") (class "Default")
      (node (ref "U9") (pin "6") (pinfunction "RESERVED_6") (pintype "passive"))
    )
    (net (code "64") (name "unconnected-(U9A-RESERVED-Pad7)") (class "Default")
      (node (ref "U9") (pin "7") (pinfunction "RESERVED_7") (pintype "passive"))
    )
    (net (code "65") (name "unconnected-(U9A-RESERVED-Pad8)") (class "Default")
      (node (ref "U9") (pin "8") (pinfunction "RESERVED_8") (pintype "passive"))
    )
    (net (code "66") (name "unconnected-(U9A-RESERVED-Pad9)") (class "Default")
      (node (ref "U9") (pin "9") (pinfunction "RESERVED_9") (pintype "passive"))
    )
    (net (code "67") (name "unconnected-(U9A-RESERVED-Pad10)") (class "Default")
      (node (ref "U9") (pin "10") (pinfunction "RESERVED_10") (pintype "passive"))
    )
    (net (code "68") (name "unconnected-(U9A-RESERVED-Pad11)") (class "Default")
      (node (ref "U9") (pin "11") (pinfunction "RESERVED_11") (pintype "passive"))
    )
    (net (code "69") (name "unconnected-(U9A-RESERVED-Pad12)") (class "Default")
      (node (ref "U9") (pin "12") (pinfunction "RESERVED_12") (pintype "passive"))
    )
    (net (code "70") (name "unconnected-(U9A-RESERVED-Pad13)") (class "Default")
      (node (ref "U9") (pin "13") (pinfunction "RESERVED_13") (pintype "passive"))
    )
    (net (code "71") (name "unconnected-(U9A-RESERVED-Pad14)") (class "Default")
      (node (ref "U9") (pin "14") (pinfunction "RESERVED_14") (pintype "passive"))
    )
    (net (code "72") (name "unconnected-(U9A-RESERVED-Pad16)") (class "Default")
      (node (ref "U9") (pin "16") (pinfunction "RESERVED_16") (pintype "passive"))
    )
    (net (code "73") (name "unconnected-(U9A-RESERVED-Pad17)") (class "Default")
      (node (ref "U9") (pin "17") (pinfunction "RESERVED_17") (pintype "passive"))
    )
    (net (code "74") (name "unconnected-(U9A-RESERVED-Pad22)") (class "Default")
      (node (ref "U9") (pin "22") (pinfunction "RESERVED_22") (pintype "passive"))
    )
    (net (code "75") (name "unconnected-(U9A-RESERVED-Pad23)") (class "Default")
      (node (ref "U9") (pin "23") (pinfunction "RESERVED_23") (pintype "passive"))
    )
    (net (code "76") (name "unconnected-(U9A-RESERVED-Pad24)") (class "Default")
      (node (ref "U9") (pin "24") (pinfunction "RESERVED_24") (pintype "passive"))
    )
    (net (code "77") (name "unconnected-(U9A-RESERVED-Pad25)") (class "Default")
      (node (ref "U9") (pin "25") (pinfunction "RESERVED_25") (pintype "passive"))
    )
    (net (code "78") (name "unconnected-(U9A-RESERVED-Pad27)") (class "Default")
      (node (ref "U9") (pin "27") (pinfunction "RESERVED_27") (pintype "passive"))
    )
    (net (code "79") (name "unconnected-(U9A-RESERVED-Pad28)") (class "Default")
      (node (ref "U9") (pin "28") (pinfunction "RESERVED_28") (pintype "passive"))
    )
    (net (code "80") (name "unconnected-(U9A-RESERVED-Pad31)") (class "Default")
      (node (ref "U9") (pin "31") (pinfunction "RESERVED_31") (pintype "passive"))
    )
    (net (code "81") (name "unconnected-(U9A-RESERVED-Pad32)") (class "Default")
      (node (ref "U9") (pin "32") (pinfunction "RESERVED_32") (pintype "passive"))
    )
    (net (code "82") (name "unconnected-(U9A-RESERVED-Pad33)") (class "Default")
      (node (ref "U9") (pin "33") (pinfunction "RESERVED_33") (pintype "passive"))
    )
    (net (code "83") (name "unconnected-(U9A-RESERVED-Pad35)") (class "Default")
      (node (ref "U9") (pin "35") (pinfunction "RESERVED_35") (pintype "passive"))
    )
    (net (code "84") (name "unconnected-(U9A-RESERVED-Pad36)") (class "Default")
      (node (ref "U9") (pin "36") (pinfunction "RESERVED_36") (pintype "passive"))
    )
    (net (code "85") (name "unconnected-(U9A-RESERVED-Pad37)") (class "Default")
      (node (ref "U9") (pin "37") (pinfunction "RESERVED_37") (pintype "passive"))
    )
    (net (code "86") (name "unconnected-(U9A-RESERVED-Pad44)") (class "Default")
      (node (ref "U9") (pin "44") (pinfunction "RESERVED_44") (pintype "passive"))
    )
    (net (code "87") (name "unconnected-(U9A-RESERVED-Pad49)") (class "Default")
      (node (ref "U9") (pin "49") (pinfunction "RESERVED_49") (pintype "passive"))
    )
    (net (code "88") (name "unconnected-(U9A-RESERVED-Pad50)") (class "Default")
      (node (ref "U9") (pin "50") (pinfunction "RESERVED_50") (pintype "passive"))
    )
    (net (code "89") (name "unconnected-(U9A-RI-Pad34)") (class "Default")
      (node (ref "U9") (pin "34") (pinfunction "RI_34") (pintype "passive"))
    )
    (net (code "90") (name "unconnected-(U9A-SWD_CLK-Pad4)") (class "Default")
      (node (ref "U9") (pin "4") (pinfunction "SWD_CLK_4") (pintype "passive"))
    )
    (net (code "91") (name "unconnected-(U9A-SWD_DATA-Pad3)") (class "Default")
      (node (ref "U9") (pin "3") (pinfunction "SWD_DATA_3") (pintype "passive"))
    )
    (net (code "92") (name "unconnected-(U9B-RESERVED-Pad55)") (class "Default")
      (node (ref "U9") (pin "55") (pinfunction "RESERVED_55") (pintype "passive"))
    )
    (net (code "93") (name "unconnected-(U9B-RESERVED-Pad56)") (class "Default")
      (node (ref "U9") (pin "56") (pinfunction "RESERVED_56") (pintype "passive"))
    )
    (net (code "94") (name "unconnected-(U9B-RESERVED-Pad57)") (class "Default")
      (node (ref "U9") (pin "57") (pinfunction "RESERVED_57") (pintype "passive"))
    )
    (net (code "95") (name "unconnected-(U9B-RESERVED-Pad58)") (class "Default")
      (node (ref "U9") (pin "58") (pinfunction "RESERVED_58") (pintype "passive"))
    )
    (net (code "96") (name "unconnected-(U9B-RESERVED-Pad67)") (class "Default")
      (node (ref "U9") (pin "67") (pinfunction "RESERVED_67") (pintype "passive"))
    )
    (net (code "97") (name "unconnected-(U9B-RESERVED-Pad68)") (class "Default")
      (node (ref "U9") (pin "68") (pinfunction "RESERVED_68") (pintype "passive"))
    )
    (net (code "98") (name "unconnected-(U9B-RESERVED-Pad69)") (class "Default")
      (node (ref "U9") (pin "69") (pinfunction "RESERVED_69") (pintype "passive"))
    )
    (net (code "99") (name "unconnected-(U9B-RESERVED-Pad70)") (class "Default")
      (node (ref "U9") (pin "70") (pinfunction "RESERVED_70") (pintype "passive"))
    )
    (net (code "100") (name "unconnected-(U9B-RESERVED-Pad75)") (class "Default")
      (node (ref "U9") (pin "75") (pinfunction "RESERVED_75") (pintype "passive"))
    )
    (net (code "101") (name "unconnected-(U9B-RESERVED-Pad76)") (class "Default")
      (node (ref "U9") (pin "76") (pinfunction "RESERVED_76") (pintype "passive"))
    )
    (net (code "102") (name "unconnected-(U9B-RESERVED-Pad77)") (class "Default")
      (node (ref "U9") (pin "77") (pinfunction "RESERVED_77") (pintype "passive"))
    )
    (net (code "103") (name "unconnected-(U9B-RESERVED-Pad78)") (class "Default")
      (node (ref "U9") (pin "78") (pinfunction "RESERVED_78") (pintype "passive"))
    )
    (net (code "104") (name "unconnected-(U9B-RESERVED-Pad79)") (class "Default")
      (node (ref "U9") (pin "79") (pinfunction "RESERVED_79") (pintype "passive"))
    )
    (net (code "105") (name "unconnected-(U9B-RESERVED-Pad80)") (class "Default")
      (node (ref "U9") (pin "80") (pinfunction "RESERVED_80") (pintype "passive"))
    )
    (net (code "106") (name "unconnected-(U9B-RESERVED-Pad84)") (class "Default")
      (node (ref "U9") (pin "84") (pinfunction "RESERVED_84") (pintype "passive"))
    )
    (net (code "107") (name "unconnected-(U9B-RESERVED-Pad85)") (class "Default")
      (node (ref "U9") (pin "85") (pinfunction "RESERVED_85") (pintype "passive"))
    )
    (net (code "108") (name "unconnected-(U9B-RESERVED-Pad86)") (class "Default")
      (node (ref "U9") (pin "86") (pinfunction "RESERVED_86") (pintype "passive"))
    )
    (net (code "109") (name "unconnected-(U9B-RESERVED-Pad87)") (class "Default")
      (node (ref "U9") (pin "87") (pinfunction "RESERVED_87") (pintype "passive"))
    )
    (net (code "110") (name "unconnected-(U9B-RESERVED-Pad88)") (class "Default")
      (node (ref "U9") (pin "88") (pinfunction "RESERVED_88") (pintype "passive"))
    )
    (net (code "111") (name "unconnected-(U9B-RESERVED-Pad89)") (class "Default")
      (node (ref "U9") (pin "89") (pinfunction "RESERVED_89") (pintype "passive"))
    )
    (net (code "112") (name "unconnected-(U9B-RESERVED-Pad90)") (class "Default")
      (node (ref "U9") (pin "90") (pinfunction "RESERVED_90") (pintype "passive"))
    )
    (net (code "113") (name "unconnected-(U9B-RESERVED-Pad91)") (class "Default")
      (node (ref "U9") (pin "91") (pinfunction "RESERVED_91") (pintype "passive"))
    )
  )
)
